# Mechanical.net
KiCad netlist of a schematic drawn in Altium Designer
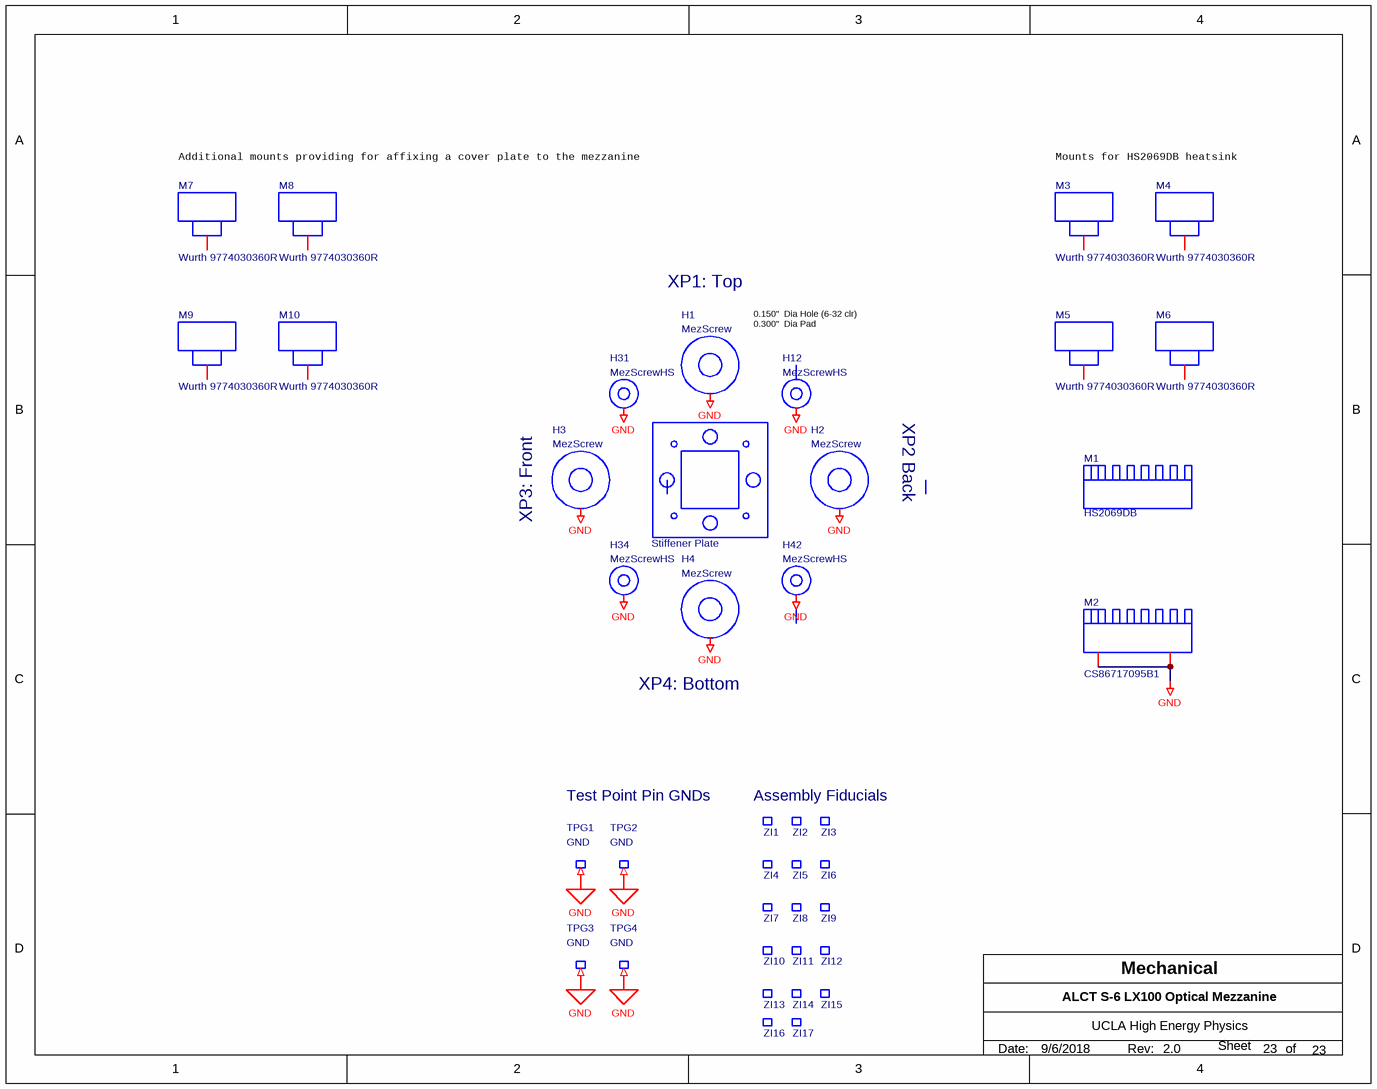
[diagram p0: Mechanical.SchDoc]

(export (version "E")
  (design (tool "Eeschema 10.0.6"))
  (components
    (comp (ref "H1")
      (value "MezScrew")
      (footprint "MC_S6/TH/SCREW_BASE")
      (libsource (lib "ALCT_MEZ_SPARTAN6_Library") (part "MezScrew"))
    )
    (comp (ref "H2")
      (value "MezScrew")
      (footprint "MC_S6/TH/SCREW_BASE")
      (libsource (lib "ALCT_MEZ_SPARTAN6_Library") (part "MezScrew"))
    )
    (comp (ref "H3")
      (value "MezScrew")
      (footprint "MC_S6/TH/SCREW_BASE")
      (libsource (lib "ALCT_MEZ_SPARTAN6_Library") (part "MezScrew"))
    )
    (comp (ref "H4")
      (value "MezScrew")
      (footprint "MC_S6/TH/SCREW_BASE")
      (libsource (lib "ALCT_MEZ_SPARTAN6_Library") (part "MezScrew"))
    )
    (comp (ref "H12")
      (value "MezScrewHS")
      (footprint "MC_S6/TH/SCREW_PLATE")
      (libsource (lib "ALCT_MEZ_SPARTAN6_Library") (part "MezScrewHS"))
    )
    (comp (ref "H31")
      (value "MezScrewHS")
      (footprint "MC_S6/TH/SCREW_PLATE")
      (libsource (lib "ALCT_MEZ_SPARTAN6_Library") (part "MezScrewHS"))
    )
    (comp (ref "H34")
      (value "MezScrewHS")
      (footprint "MC_S6/TH/SCREW_PLATE")
      (libsource (lib "ALCT_MEZ_SPARTAN6_Library") (part "MezScrewHS"))
    )
    (comp (ref "H42")
      (value "MezScrewHS")
      (footprint "MC_S6/TH/SCREW_PLATE")
      (libsource (lib "ALCT_MEZ_SPARTAN6_Library") (part "MezScrewHS"))
    )
    (comp (ref "M1")
      (value "HS2069DB")
      (footprint "HS2069DB")
      (description "Heatsink 61 x 58 x 12mm")
      (libsource (lib "ALCT_MEZ_SPARTAN6_Library") (part "HS2069DB"))
    )
    (comp (ref "M2")
      (value "CS86717095B1")
      (footprint "CS86717095B1")
      (description "Heatsink 17 x 17 x 9.5mm")
      (libsource (lib "ALCT_MEZ_SPARTAN6_Library") (part "CS86717095B1"))
    )
    (comp (ref "M3")
      (value "Wurth 9774030360R")
      (footprint "Wurth/9774020360R")
      (description "9774030360R 3mm SMD Standoff")
      (fields
        (field (name "MANUFACTURER") "Wurth Electronics")
        (field (name "MANUFACTURER PART NUMBER") "9774030360R")
      )
      (libsource (lib "ALCT_MEZ_SPARTAN6_Library") (part "Wurth/9774030360R"))
    )
    (comp (ref "M4")
      (value "Wurth 9774030360R")
      (footprint "Wurth/9774020360R")
      (description "9774030360R 3mm SMD Standoff")
      (fields
        (field (name "MANUFACTURER") "Wurth Electronics")
        (field (name "MANUFACTURER PART NUMBER") "9774030360R")
      )
      (libsource (lib "ALCT_MEZ_SPARTAN6_Library") (part "Wurth/9774030360R"))
    )
    (comp (ref "M5")
      (value "Wurth 9774030360R")
      (footprint "Wurth/9774020360R")
      (description "9774030360R 3mm SMD Standoff")
      (fields
        (field (name "MANUFACTURER") "Wurth Electronics")
        (field (name "MANUFACTURER PART NUMBER") "9774030360R")
      )
      (libsource (lib "ALCT_MEZ_SPARTAN6_Library") (part "Wurth/9774030360R"))
    )
    (comp (ref "M6")
      (value "Wurth 9774030360R")
      (footprint "Wurth/9774020360R")
      (description "9774030360R 3mm SMD Standoff")
      (fields
        (field (name "MANUFACTURER") "Wurth Electronics")
        (field (name "MANUFACTURER PART NUMBER") "9774030360R")
      )
      (libsource (lib "ALCT_MEZ_SPARTAN6_Library") (part "Wurth/9774030360R"))
    )
    (comp (ref "M7")
      (value "Wurth 9774030360R")
      (footprint "Wurth/9774020360R")
      (description "9774030360R 3mm SMD Standoff")
      (fields
        (field (name "MANUFACTURER") "Wurth Electronics")
        (field (name "MANUFACTURER PART NUMBER") "9774030360R")
      )
      (libsource (lib "ALCT_MEZ_SPARTAN6_Library") (part "Wurth/9774030360R"))
    )
    (comp (ref "M8")
      (value "Wurth 9774030360R")
      (footprint "Wurth/9774020360R")
      (description "9774030360R 3mm SMD Standoff")
      (fields
        (field (name "MANUFACTURER") "Wurth Electronics")
        (field (name "MANUFACTURER PART NUMBER") "9774030360R")
      )
      (libsource (lib "ALCT_MEZ_SPARTAN6_Library") (part "Wurth/9774030360R"))
    )
    (comp (ref "M9")
      (value "Wurth 9774030360R")
      (footprint "Wurth/9774020360R")
      (description "9774030360R 3mm SMD Standoff")
      (fields
        (field (name "MANUFACTURER") "Wurth Electronics")
        (field (name "MANUFACTURER PART NUMBER") "9774030360R")
      )
      (libsource (lib "ALCT_MEZ_SPARTAN6_Library") (part "Wurth/9774030360R"))
    )
    (comp (ref "M10")
      (value "Wurth 9774030360R")
      (footprint "Wurth/9774020360R")
      (description "9774030360R 3mm SMD Standoff")
      (fields
        (field (name "MANUFACTURER") "Wurth Electronics")
        (field (name "MANUFACTURER PART NUMBER") "9774030360R")
      )
      (libsource (lib "ALCT_MEZ_SPARTAN6_Library") (part "Wurth/9774030360R"))
    )
    (comp (ref "SP1")
      (value "Stiffener Plate")
      (footprint "MC_S6/SPLATE")
      (libsource (lib "ALCT_MEZ_SPARTAN6_Library") (part "SPlate_MC_S6"))
    )
    (comp (ref "TPG1") (value "GND") (footprint "MC_S6/TH/TPGND") (libsource (lib "*") (part "TPGND")))
    (comp (ref "TPG2") (value "GND") (footprint "MC_S6/TH/TPGND") (libsource (lib "*") (part "TPGND")))
    (comp (ref "TPG3") (value "GND") (footprint "MC_S6/TH/TPGND") (libsource (lib "*") (part "TPGND")))
    (comp (ref "TPG4") (value "GND") (footprint "MC_S6/TH/TPGND") (libsource (lib "*") (part "TPGND")))
    (comp (ref "ZI1")
      (value "Fiducial Dot")
      (footprint "MC_S6/SM/FIDUCIAL_DOT")
      (libsource (lib "ALCT_MEZ_SPARTAN6_Library") (part "Fiducial_dot"))
    )
    (comp (ref "ZI2")
      (value "Fiducial Dot")
      (footprint "MC_S6/SM/FIDUCIAL_DOT")
      (libsource (lib "ALCT_MEZ_SPARTAN6_Library") (part "Fiducial_dot"))
    )
    (comp (ref "ZI3")
      (value "Fiducial Dot")
      (footprint "MC_S6/SM/FIDUCIAL_DOT")
      (libsource (lib "ALCT_MEZ_SPARTAN6_Library") (part "Fiducial_dot"))
    )
    (comp (ref "ZI4")
      (value "Fiducial Dot")
      (footprint "MC_S6/SM/FIDUCIAL_DOT")
      (libsource (lib "ALCT_MEZ_SPARTAN6_Library") (part "Fiducial_dot"))
    )
    (comp (ref "ZI5")
      (value "Fiducial Dot")
      (footprint "MC_S6/SM/FIDUCIAL_DOT")
      (libsource (lib "ALCT_MEZ_SPARTAN6_Library") (part "Fiducial_dot"))
    )
    (comp (ref "ZI6")
      (value "Fiducial Dot")
      (footprint "MC_S6/SM/FIDUCIAL_DOT")
      (libsource (lib "ALCT_MEZ_SPARTAN6_Library") (part "Fiducial_dot"))
    )
    (comp (ref "ZI7")
      (value "Fiducial Dot")
      (footprint "MC_S6/SM/FIDUCIAL_DOT")
      (libsource (lib "ALCT_MEZ_SPARTAN6_Library") (part "Fiducial_dot"))
    )
    (comp (ref "ZI8")
      (value "Fiducial Dot")
      (footprint "MC_S6/SM/FIDUCIAL_DOT")
      (libsource (lib "ALCT_MEZ_SPARTAN6_Library") (part "Fiducial_dot"))
    )
    (comp (ref "ZI9")
      (value "Fiducial Dot")
      (footprint "MC_S6/SM/FIDUCIAL_DOT")
      (libsource (lib "ALCT_MEZ_SPARTAN6_Library") (part "Fiducial_dot"))
    )
    (comp (ref "ZI10")
      (value "Fiducial Dot")
      (footprint "MC_S6/SM/FIDUCIAL_DOT")
      (libsource (lib "ALCT_MEZ_SPARTAN6_Library") (part "Fiducial_dot"))
    )
    (comp (ref "ZI11")
      (value "Fiducial Dot")
      (footprint "MC_S6/SM/FIDUCIAL_DOT")
      (libsource (lib "ALCT_MEZ_SPARTAN6_Library") (part "Fiducial_dot"))
    )
    (comp (ref "ZI12")
      (value "Fiducial Dot")
      (footprint "MC_S6/SM/FIDUCIAL_DOT")
      (libsource (lib "ALCT_MEZ_SPARTAN6_Library") (part "Fiducial_dot"))
    )
    (comp (ref "ZI13")
      (value "Fiducial Dot")
      (footprint "MC_S6/SM/FIDUCIAL_DOT")
      (libsource (lib "ALCT_MEZ_SPARTAN6_Library") (part "Fiducial_dot"))
    )
    (comp (ref "ZI14")
      (value "Fiducial Dot")
      (footprint "MC_S6/SM/FIDUCIAL_DOT")
      (libsource (lib "ALCT_MEZ_SPARTAN6_Library") (part "Fiducial_dot"))
    )
    (comp (ref "ZI15")
      (value "Fiducial Dot")
      (footprint "MC_S6/SM/FIDUCIAL_DOT")
      (libsource (lib "ALCT_MEZ_SPARTAN6_Library") (part "Fiducial_dot"))
    )
    (comp (ref "ZI16")
      (value "Fiducial Dot")
      (footprint "MC_S6/SM/FIDUCIAL_DOT")
      (libsource (lib "ALCT_MEZ_SPARTAN6_Library") (part "Fiducial_dot"))
    )
    (comp (ref "ZI17")
      (value "Fiducial Dot")
      (footprint "MC_S6/SM/FIDUCIAL_DOT")
      (libsource (lib "ALCT_MEZ_SPARTAN6_Library") (part "Fiducial_dot"))
    )
  )
  (nets
    (net (code "1") (name "GND") (class "Default")
      (node (ref "H1") (pin "1") (pinfunction "GND_1") (pintype "power_in"))
      (node (ref "H12") (pin "1") (pinfunction "GND_1") (pintype "power_in"))
      (node (ref "H2") (pin "1") (pinfunction "GND_1") (pintype "power_in"))
      (node (ref "H3") (pin "1") (pinfunction "GND_1") (pintype "power_in"))
      (node (ref "H31") (pin "1") (pinfunction "GND_1") (pintype "power_in"))
      (node (ref "H34") (pin "1") (pinfunction "GND_1") (pintype "power_in"))
      (node (ref "H4") (pin "1") (pinfunction "GND_1") (pintype "power_in"))
      (node (ref "H42") (pin "1") (pinfunction "GND_1") (pintype "power_in"))
      (node (ref "M2") (pin "1") (pinfunction "1_1") (pintype "passive"))
      (node (ref "M2") (pin "2") (pinfunction "4_2") (pintype "passive"))
      (node (ref "TPG1") (pin "1") (pinfunction "In_1") (pintype "input"))
      (node (ref "TPG2") (pin "1") (pinfunction "In_1") (pintype "input"))
      (node (ref "TPG3") (pin "1") (pinfunction "In_1") (pintype "input"))
      (node (ref "TPG4") (pin "1") (pinfunction "In_1") (pintype "input"))
    )
    (net (code "2") (name "unconnected-(M3-Pad1)") (class "Default")
      (node (ref "M3") (pin "1") (pinfunction "1_1") (pintype "passive"))
    )
    (net (code "3") (name "unconnected-(M4-Pad1)") (class "Default")
      (node (ref "M4") (pin "1") (pinfunction "1_1") (pintype "passive"))
    )
    (net (code "4") (name "unconnected-(M5-Pad1)") (class "Default")
      (node (ref "M5") (pin "1") (pinfunction "1_1") (pintype "passive"))
    )
    (net (code "5") (name "unconnected-(M6-Pad1)") (class "Default")
      (node (ref "M6") (pin "1") (pinfunction "1_1") (pintype "passive"))
    )
    (net (code "6") (name "unconnected-(M7-Pad1)") (class "Default")
      (node (ref "M7") (pin "1") (pinfunction "1_1") (pintype "passive"))
    )
    (net (code "7") (name "unconnected-(M8-Pad1)") (class "Default")
      (node (ref "M8") (pin "1") (pinfunction "1_1") (pintype "passive"))
    )
    (net (code "8") (name "unconnected-(M9-Pad1)") (class "Default")
      (node (ref "M9") (pin "1") (pinfunction "1_1") (pintype "passive"))
    )
    (net (code "9") (name "unconnected-(M10-Pad1)") (class "Default")
      (node (ref "M10") (pin "1") (pinfunction "1_1") (pintype "passive"))
    )
    (net (code "10") (name "unconnected-(ZI1-NC-Pad1)") (class "Default")
      (node (ref "ZI1") (pin "1") (pinfunction "NC_1") (pintype "passive"))
    )
    (net (code "11") (name "unconnected-(ZI2-NC-Pad1)") (class "Default")
      (node (ref "ZI2") (pin "1") (pinfunction "NC_1") (pintype "passive"))
    )
    (net (code "12") (name "unconnected-(ZI3-NC-Pad1)") (class "Default")
      (node (ref "ZI3") (pin "1") (pinfunction "NC_1") (pintype "passive"))
    )
    (net (code "13") (name "unconnected-(ZI4-NC-Pad1)") (class "Default")
      (node (ref "ZI4") (pin "1") (pinfunction "NC_1") (pintype "passive"))
    )
    (net (code "14") (name "unconnected-(ZI5-NC-Pad1)") (class "Default")
      (node (ref "ZI5") (pin "1") (pinfunction "NC_1") (pintype "passive"))
    )
    (net (code "15") (name "unconnected-(ZI6-NC-Pad1)") (class "Default")
      (node (ref "ZI6") (pin "1") (pinfunction "NC_1") (pintype "passive"))
    )
    (net (code "16") (name "unconnected-(ZI7-NC-Pad1)") (class "Default")
      (node (ref "ZI7") (pin "1") (pinfunction "NC_1") (pintype "passive"))
    )
    (net (code "17") (name "unconnected-(ZI8-NC-Pad1)") (class "Default")
      (node (ref "ZI8") (pin "1") (pinfunction "NC_1") (pintype "passive"))
    )
    (net (code "18") (name "unconnected-(ZI9-NC-Pad1)") (class "Default")
      (node (ref "ZI9") (pin "1") (pinfunction "NC_1") (pintype "passive"))
    )
    (net (code "19") (name "unconnected-(ZI10-NC-Pad1)") (class "Default")
      (node (ref "ZI10") (pin "1") (pinfunction "NC_1") (pintype "passive"))
    )
    (net (code "20") (name "unconnected-(ZI11-NC-Pad1)") (class "Default")
      (node (ref "ZI11") (pin "1") (pinfunction "NC_1") (pintype "passive"))
    )
    (net (code "21") (name "unconnected-(ZI12-NC-Pad1)") (class "Default")
      (node (ref "ZI12") (pin "1") (pinfunction "NC_1") (pintype "passive"))
    )
    (net (code "22") (name "unconnected-(ZI13-NC-Pad1)") (class "Default")
      (node (ref "ZI13") (pin "1") (pinfunction "NC_1") (pintype "passive"))
    )
    (net (code "23") (name "unconnected-(ZI14-NC-Pad1)") (class "Default")
      (node (ref "ZI14") (pin "1") (pinfunction "NC_1") (pintype "passive"))
    )
    (net (code "24") (name "unconnected-(ZI15-NC-Pad1)") (class "Default")
      (node (ref "ZI15") (pin "1") (pinfunction "NC_1") (pintype "passive"))
    )
    (net (code "25") (name "unconnected-(ZI16-NC-Pad1)") (class "Default")
      (node (ref "ZI16") (pin "1") (pinfunction "NC_1") (pintype "passive"))
    )
    (net (code "26") (name "unconnected-(ZI17-NC-Pad1)") (class "Default")
      (node (ref "ZI17") (pin "1") (pinfunction "NC_1") (pintype "passive"))
    )
  )
)
